# placa_1_0.net
KiCad netlist of a schematic drawn in EAGLE
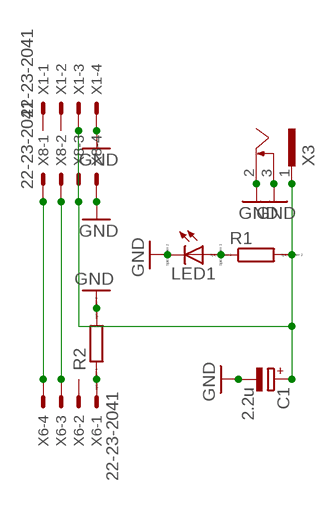
[diagram p0: schematic, sheet 1]

(export (version "E")
  (design (tool "Eeschema 10.0.6"))
  (components
    (comp (ref "C1")
      (value "2.2u")
      (footprint "eagle-import:E5-13")
      (libsource (lib "eagle-import") (part "CPOL-EUE5-13"))
    )
    (comp (ref "LED1")
      (value "LED_ELD260")
      (footprint "eagle-import:LED_LD260")
      (libsource (lib "eagle-import") (part "LED_ELD260"))
    )
    (comp (ref "R1")
      (value "R0207/10")
      (footprint "eagle-import:0207_10")
      (libsource (lib "eagle-import") (part "R0207/10"))
    )
    (comp (ref "R2")
      (value "R0207/10")
      (footprint "eagle-import:0207_10")
      (libsource (lib "eagle-import") (part "R0207/10"))
    )
    (comp (ref "X1")
      (value "22-23-2041")
      (footprint "eagle-import:22-23-2041")
      (fields (field (name "MF") "MOLEX"))
      (libsource (lib "eagle-import") (part "22-23-2041"))
    )
    (comp (ref "X3")
      (value "SCD-014A")
      (footprint "eagle-import:SCD-014-A")
      (libsource (lib "eagle-import") (part "SCD-014A"))
    )
    (comp (ref "X6")
      (value "22-23-2041")
      (footprint "eagle-import:22-23-2041")
      (fields (field (name "MF") "MOLEX"))
      (libsource (lib "eagle-import") (part "22-23-2041"))
    )
    (comp (ref "X8")
      (value "22-23-2041")
      (footprint "eagle-import:22-23-2041")
      (fields (field (name "MF") "MOLEX"))
      (libsource (lib "eagle-import") (part "22-23-2041"))
    )
  )
  (nets
    (net (code "1") (name "GND") (class "Default")
      (node (ref "C1") (pin "-") (pinfunction "-_-") (pintype "passive"))
      (node (ref "LED1") (pin "K") (pinfunction "C_K") (pintype "passive"))
      (node (ref "R2") (pin "2") (pinfunction "2_2") (pintype "passive"))
      (node (ref "X1") (pin "4") (pinfunction "S_4") (pintype "passive"))
      (node (ref "X3") (pin "2") (pinfunction "2_2") (pintype "passive"))
      (node (ref "X3") (pin "3") (pinfunction "3_3") (pintype "passive"))
      (node (ref "X8") (pin "4") (pinfunction "S_4") (pintype "passive"))
    )
    (net (code "2") (name "Net-(LED1-PadA)") (class "Default")
      (node (ref "LED1") (pin "A") (pinfunction "A_A") (pintype "passive"))
      (node (ref "R1") (pin "1") (pinfunction "1_1") (pintype "passive"))
    )
    (net (code "3") (name "Net-(X1C-S)") (class "Default")
      (node (ref "C1") (pin "+") (pinfunction "+_+") (pintype "passive"))
      (node (ref "R1") (pin "2") (pinfunction "2_2") (pintype "passive"))
      (node (ref "X1") (pin "3") (pinfunction "S_3") (pintype "passive"))
      (node (ref "X3") (pin "1") (pinfunction "1_1") (pintype "passive"))
      (node (ref "X8") (pin "3") (pinfunction "S_3") (pintype "passive"))
    )
    (net (code "4") (name "Net-(X6A-S)") (class "Default")
      (node (ref "R2") (pin "1") (pinfunction "1_1") (pintype "passive"))
      (node (ref "X6") (pin "1") (pinfunction "S_1") (pintype "passive"))
    )
    (net (code "5") (name "Net-(X6C-S)") (class "Default")
      (node (ref "X6") (pin "3") (pinfunction "S_3") (pintype "passive"))
      (node (ref "X8") (pin "2") (pinfunction "S_2") (pintype "passive"))
    )
    (net (code "6") (name "Net-(X6D-S)") (class "Default")
      (node (ref "X6") (pin "4") (pinfunction "S_4") (pintype "passive"))
      (node (ref "X8") (pin "1") (pinfunction "S_1") (pintype "passive"))
    )
    (net (code "7") (name "unconnected-(X1A-S-Pad1)") (class "Default")
      (node (ref "X1") (pin "1") (pinfunction "S_1") (pintype "passive"))
    )
    (net (code "8") (name "unconnected-(X1B-S-Pad2)") (class "Default")
      (node (ref "X1") (pin "2") (pinfunction "S_2") (pintype "passive"))
    )
    (net (code "9") (name "unconnected-(X6B-S-Pad2)") (class "Default")
      (node (ref "X6") (pin "2") (pinfunction "S_2") (pintype "passive"))
    )
  )
)
